# jack_driver_2.net
KiCad netlist of a schematic drawn in Altium Designer
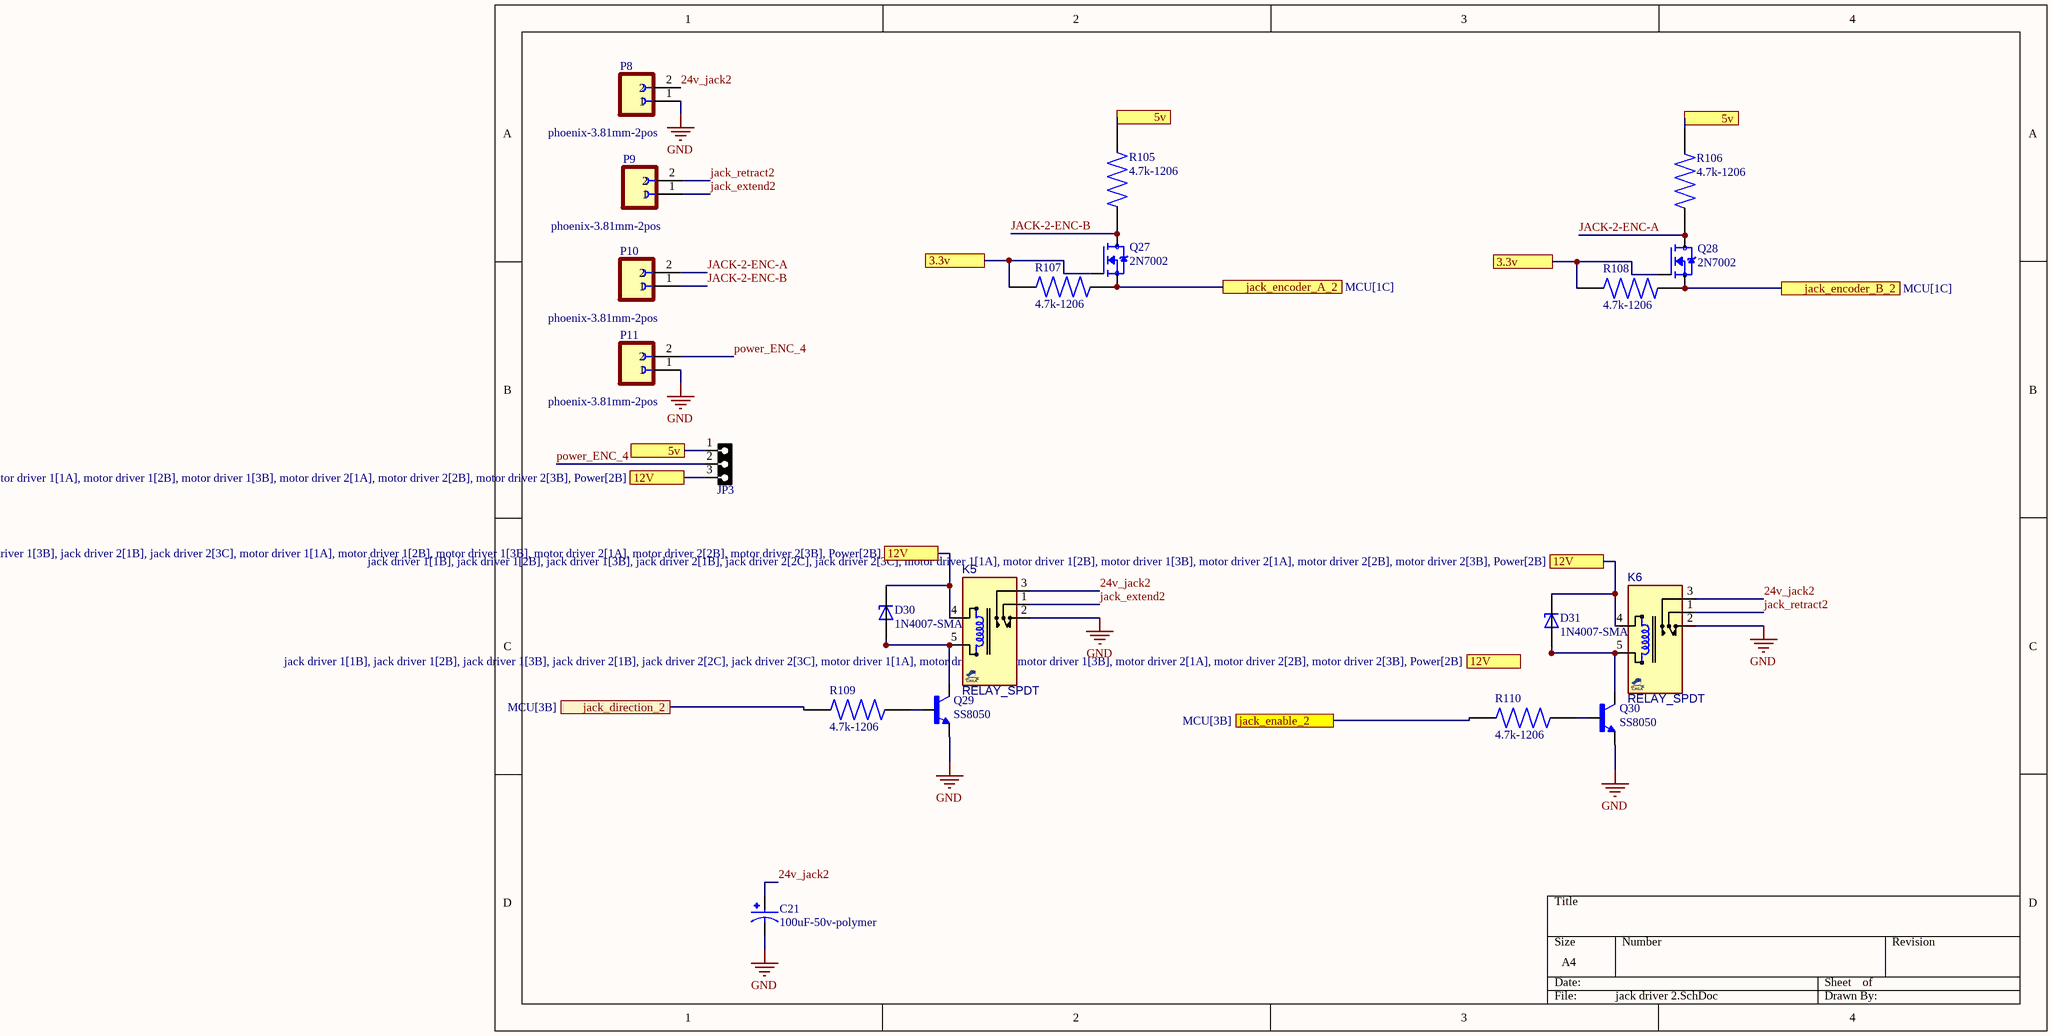
[diagram p0: jack driver 2.SchDoc]

(export (version "E")
  (design (tool "Eeschema 10.0.6"))
  (components
    (comp (ref "C21")
      (value "100uF-50v-polymer")
      (footprint "CAP_EEEFN1H101L")
      (description "CAP ALUM 100UF 20% 50V SMD")
      (fields (field (name "MF") "Panasonic") (field (name "MP") "EEEFN1H101L"))
      (libsource (lib "100uF_50v") (part "EEEFN1H101L"))
    )
    (comp (ref "D30")
      (value "1N4007-SMA")
      (footprint "DIOM4325X250N")
      (description "400W, 30.4V, 5%, Unidirectional, TVS")
      (fields (field (name "MF") "Taiwan Semiconductor") (field (name "MP") "SMAJ26A"))
      (libsource (lib "diode-sma") (part "SMAJ26A"))
    )
    (comp (ref "D31")
      (value "1N4007-SMA")
      (footprint "DIOM4325X250N")
      (description "400W, 30.4V, 5%, Unidirectional, TVS")
      (fields (field (name "MF") "Taiwan Semiconductor") (field (name "MP") "SMAJ26A"))
      (libsource (lib "diode-sma") (part "SMAJ26A"))
    )
    (comp (ref "JP3")
      (value "HDRF3")
      (footprint "HDRLP_F_1X3")
      (description "CONN, HEADER, Male, pitch: 2.54mm, 3POS")
      (libsource (lib "conn_2.54mm_lp") (part "HDRLP_F_1X3"))
    )
    (comp (ref "K5")
      (value "RELAY_SPDT")
      (footprint "REL_SPDT_5_1512")
      (description "Relay, SPDT, 5P, 15.4X12.1mm, 16V/30A")
      (fields (field (name "MANF") "OMRON") (field (name "MANF_P#") "G8QN-1C4 DC12"))
      (libsource (lib "relay") (part "RELAY_SPDT_5_1512_G8QN"))
    )
    (comp (ref "K6")
      (value "RELAY_SPDT")
      (footprint "REL_SPDT_5_1512")
      (description "Relay, SPDT, 5P, 15.4X12.1mm, 16V/30A")
      (fields (field (name "MANF") "OMRON") (field (name "MANF_P#") "G8QN-1C4 DC12"))
      (libsource (lib "relay") (part "RELAY_SPDT_5_1512_G8QN"))
    )
    (comp (ref "P8")
      (value "phoenix-3.81mm-2pos")
      (footprint "PHOENIX_1803578")
      (description "2 Position Terminal Block Plug, Female Sockets 0.150 (3.81mm) 180Â° Free Hanging (In-Line)")
      (fields (field (name "MF") "Phoenix Contact") (field (name "MP") "1803578"))
      (libsource (lib "terminal-phoenix-3.81mm-2pos") (part "1803578"))
    )
    (comp (ref "P9")
      (value "phoenix-3.81mm-2pos")
      (footprint "PHOENIX_1803578")
      (description "2 Position Terminal Block Plug, Female Sockets 0.150 (3.81mm) 180Â° Free Hanging (In-Line)")
      (fields (field (name "MF") "Phoenix Contact") (field (name "MP") "1803578"))
      (libsource (lib "terminal-phoenix-3.81mm-2pos") (part "1803578"))
    )
    (comp (ref "P10")
      (value "phoenix-3.81mm-2pos")
      (footprint "PHOENIX_1803578")
      (description "2 Position Terminal Block Plug, Female Sockets 0.150 (3.81mm) 180Â° Free Hanging (In-Line)")
      (fields (field (name "MF") "Phoenix Contact") (field (name "MP") "1803578"))
      (libsource (lib "terminal-phoenix-3.81mm-2pos") (part "1803578"))
    )
    (comp (ref "P11")
      (value "phoenix-3.81mm-2pos")
      (footprint "PHOENIX_1803578")
      (description "2 Position Terminal Block Plug, Female Sockets 0.150 (3.81mm) 180Â° Free Hanging (In-Line)")
      (fields (field (name "MF") "Phoenix Contact") (field (name "MP") "1803578"))
      (libsource (lib "terminal-phoenix-3.81mm-2pos") (part "1803578"))
    )
    (comp (ref "Q27")
      (value "2N7002")
      (footprint "SOT95P240X111-3N")
      (description "N-Channel 60V 280mA (Ta) 350mW (Ta) Surface Mount SOT-23-3 (TO-236)")
      (fields (field (name "MF") "{'manufacturer': u'onsemi'}"))
      (libsource (lib "2N7002-SOT23") (part "2N7002"))
    )
    (comp (ref "Q28")
      (value "2N7002")
      (footprint "SOT95P240X111-3N")
      (description "N-Channel 60V 280mA (Ta) 350mW (Ta) Surface Mount SOT-23-3 (TO-236)")
      (fields (field (name "MF") "{'manufacturer': u'onsemi'}"))
      (libsource (lib "2N7002-SOT23") (part "2N7002"))
    )
    (comp (ref "Q29")
      (value "SS8050")
      (footprint "TRANS_SS8050-G")
      (description "Bipolar (BJT) Transistor NPN 25 V 1.5 A 100MHz 300 mW Surface Mount SOT-23-3")
      (fields (field (name "DIGI-KEY_PART_NUMBER") "641-1790-2-ND") (field (name "MP") "SS8050G"))
      (libsource (lib "SS8050-G") (part "SS8050-G"))
    )
    (comp (ref "Q30")
      (value "SS8050")
      (footprint "TRANS_SS8050-G")
      (description "Bipolar (BJT) Transistor NPN 25 V 1.5 A 100MHz 300 mW Surface Mount SOT-23-3")
      (fields (field (name "DIGI-KEY_PART_NUMBER") "641-1790-2-ND") (field (name "MP") "SS8050G"))
      (libsource (lib "SS8050-G") (part "SS8050-G"))
    )
    (comp (ref "R105")
      (value "4.7k-1206")
      (footprint "RESC3015X65N")
      (description "Res Thin Film 1206 10K Ohm 0.1% 1/8W Â±25ppm/Â°C Molded SMD SMD Paper T/R")
      (fields (field (name "MF") "TE Connectivity") (field (name "MP") "CPF1206B10KE1"))
      (libsource (lib "resistor-1206") (part "CPF1206B10KE1"))
    )
    (comp (ref "R106")
      (value "4.7k-1206")
      (footprint "RESC3015X65N")
      (description "Res Thin Film 1206 10K Ohm 0.1% 1/8W Â±25ppm/Â°C Molded SMD SMD Paper T/R")
      (fields (field (name "MF") "TE Connectivity") (field (name "MP") "CPF1206B10KE1"))
      (libsource (lib "resistor-1206") (part "CPF1206B10KE1"))
    )
    (comp (ref "R107")
      (value "4.7k-1206")
      (footprint "RESC3015X65N")
      (description "Res Thin Film 1206 10K Ohm 0.1% 1/8W Â±25ppm/Â°C Molded SMD SMD Paper T/R")
      (fields (field (name "MF") "TE Connectivity") (field (name "MP") "CPF1206B10KE1"))
      (libsource (lib "resistor-1206") (part "CPF1206B10KE1"))
    )
    (comp (ref "R108")
      (value "4.7k-1206")
      (footprint "RESC3015X65N")
      (description "Res Thin Film 1206 10K Ohm 0.1% 1/8W Â±25ppm/Â°C Molded SMD SMD Paper T/R")
      (fields (field (name "MF") "TE Connectivity") (field (name "MP") "CPF1206B10KE1"))
      (libsource (lib "resistor-1206") (part "CPF1206B10KE1"))
    )
    (comp (ref "R109")
      (value "4.7k-1206")
      (footprint "RESC3015X65N")
      (description "Res Thin Film 1206 10K Ohm 0.1% 1/8W Â±25ppm/Â°C Molded SMD SMD Paper T/R")
      (fields (field (name "MF") "TE Connectivity") (field (name "MP") "CPF1206B10KE1"))
      (libsource (lib "resistor-1206") (part "CPF1206B10KE1"))
    )
    (comp (ref "R110")
      (value "4.7k-1206")
      (footprint "RESC3015X65N")
      (description "Res Thin Film 1206 10K Ohm 0.1% 1/8W Â±25ppm/Â°C Molded SMD SMD Paper T/R")
      (fields (field (name "MF") "TE Connectivity") (field (name "MP") "CPF1206B10KE1"))
      (libsource (lib "resistor-1206") (part "CPF1206B10KE1"))
    )
  )
  (nets
    (net (code "1") (name "/3.3v") (class "Default")
      (node (ref "Q27") (pin "1") (pinfunction "G_1") (pintype "passive"))
      (node (ref "Q28") (pin "1") (pinfunction "G_1") (pintype "passive"))
      (node (ref "R107") (pin "2") (pinfunction "2_2") (pintype "passive"))
      (node (ref "R108") (pin "2") (pinfunction "2_2") (pintype "passive"))
    )
    (net (code "2") (name "/5v") (class "Default")
      (node (ref "JP3") (pin "1") (pinfunction "1_1") (pintype "passive"))
      (node (ref "R105") (pin "2") (pinfunction "2_2") (pintype "passive"))
      (node (ref "R106") (pin "2") (pinfunction "2_2") (pintype "passive"))
    )
    (net (code "3") (name "/12V") (class "Default")
      (node (ref "D30") (pin "C") (pinfunction "C_C") (pintype "passive"))
      (node (ref "D31") (pin "C") (pinfunction "C_C") (pintype "passive"))
      (node (ref "JP3") (pin "3") (pinfunction "3_3") (pintype "passive"))
      (node (ref "K5") (pin "4") (pinfunction "T1_4") (pintype "passive"))
      (node (ref "K6") (pin "4") (pinfunction "T1_4") (pintype "passive"))
    )
    (net (code "4") (name "/24v_jack2") (class "Default")
      (node (ref "C21") (pin "1") (pinfunction "1_1") (pintype "passive"))
      (node (ref "K5") (pin "3") (pinfunction "NO_3") (pintype "passive"))
      (node (ref "K6") (pin "3") (pinfunction "NO_3") (pintype "passive"))
      (node (ref "P8") (pin "2") (pinfunction "2_2") (pintype "passive"))
    )
    (net (code "5") (name "/JACK-2-ENC-A") (class "Default")
      (node (ref "P10") (pin "2") (pinfunction "2_2") (pintype "passive"))
      (node (ref "Q28") (pin "3") (pinfunction "D_3") (pintype "passive"))
      (node (ref "R106") (pin "1") (pinfunction "1_1") (pintype "passive"))
    )
    (net (code "6") (name "/JACK-2-ENC-B") (class "Default")
      (node (ref "P10") (pin "1") (pinfunction "1_1") (pintype "passive"))
      (node (ref "Q27") (pin "3") (pinfunction "D_3") (pintype "passive"))
      (node (ref "R105") (pin "1") (pinfunction "1_1") (pintype "passive"))
    )
    (net (code "7") (name "/jack_direction_2") (class "Default")
      (node (ref "R109") (pin "2") (pinfunction "2_2") (pintype "passive"))
    )
    (net (code "8") (name "/jack_enable_2") (class "Default")
      (node (ref "R110") (pin "2") (pinfunction "2_2") (pintype "passive"))
    )
    (net (code "9") (name "/jack_encoder_A_2") (class "Default")
      (node (ref "Q27") (pin "2") (pinfunction "S_2") (pintype "passive"))
      (node (ref "R107") (pin "1") (pinfunction "1_1") (pintype "passive"))
    )
    (net (code "10") (name "/jack_encoder_B_2") (class "Default")
      (node (ref "Q28") (pin "2") (pinfunction "S_2") (pintype "passive"))
      (node (ref "R108") (pin "1") (pinfunction "1_1") (pintype "passive"))
    )
    (net (code "11") (name "/jack_extend2") (class "Default")
      (node (ref "K5") (pin "1") (pinfunction "COM_1") (pintype "passive"))
      (node (ref "P9") (pin "1") (pinfunction "1_1") (pintype "passive"))
    )
    (net (code "12") (name "/jack_retract2") (class "Default")
      (node (ref "K6") (pin "1") (pinfunction "COM_1") (pintype "passive"))
      (node (ref "P9") (pin "2") (pinfunction "2_2") (pintype "passive"))
    )
    (net (code "13") (name "/power_ENC_4") (class "Default")
      (node (ref "JP3") (pin "2") (pinfunction "2_2") (pintype "passive"))
      (node (ref "P11") (pin "2") (pinfunction "2_2") (pintype "passive"))
    )
    (net (code "14") (name "GND") (class "Default")
      (node (ref "C21") (pin "2") (pinfunction "2_2") (pintype "passive"))
      (node (ref "K5") (pin "2") (pinfunction "NC_2") (pintype "passive"))
      (node (ref "K6") (pin "2") (pinfunction "NC_2") (pintype "passive"))
      (node (ref "P11") (pin "1") (pinfunction "1_1") (pintype "passive"))
      (node (ref "P8") (pin "1") (pinfunction "1_1") (pintype "passive"))
      (node (ref "Q29") (pin "2") (pinfunction "E_2") (pintype "passive"))
      (node (ref "Q30") (pin "2") (pinfunction "E_2") (pintype "passive"))
    )
    (net (code "15") (name "Net-(K5-T2)") (class "Default")
      (node (ref "D30") (pin "A") (pinfunction "A_A") (pintype "passive"))
      (node (ref "K5") (pin "5") (pinfunction "T2_5") (pintype "passive"))
      (node (ref "Q29") (pin "3") (pinfunction "C_3") (pintype "passive"))
    )
    (net (code "16") (name "Net-(K6-T2)") (class "Default")
      (node (ref "D31") (pin "A") (pinfunction "A_A") (pintype "passive"))
      (node (ref "K6") (pin "5") (pinfunction "T2_5") (pintype "passive"))
      (node (ref "Q30") (pin "3") (pinfunction "C_3") (pintype "passive"))
    )
    (net (code "17") (name "Net-(Q29-B)") (class "Default")
      (node (ref "Q29") (pin "1") (pinfunction "B_1") (pintype "passive"))
      (node (ref "R109") (pin "1") (pinfunction "1_1") (pintype "passive"))
    )
    (net (code "18") (name "Net-(Q30-B)") (class "Default")
      (node (ref "Q30") (pin "1") (pinfunction "B_1") (pintype "passive"))
      (node (ref "R110") (pin "1") (pinfunction "1_1") (pintype "passive"))
    )
  )
)
